# uc1C.net
KiCad netlist of a schematic drawn in Altium Designer
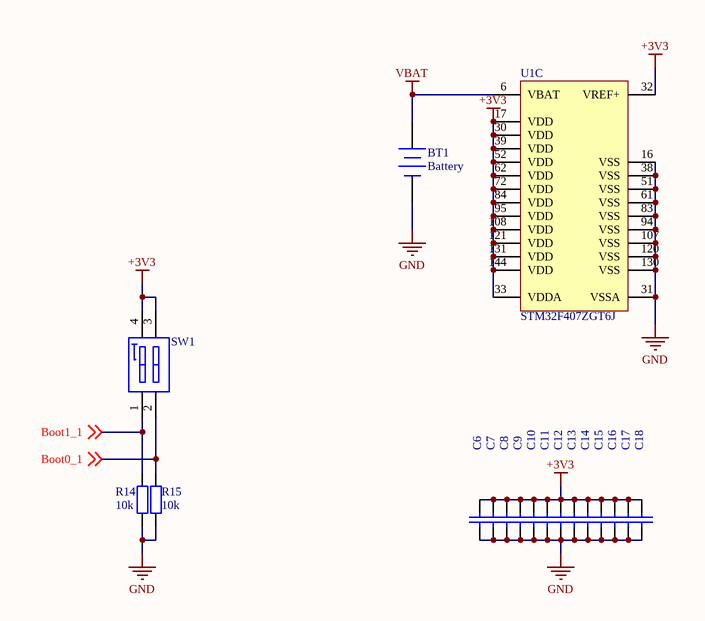
[diagram p0: uc1C.SchDoc]

(export (version "E")
  (design (tool "Eeschema 10.0.6"))
  (components
    (comp (ref "BT1")
      (value "Battery")
      (footprint "2032 SMD Holder")
      (description "Multicell Battery")
      (fields
        (field (name "MANUFACTURER") "MULTICOMP")
        (field (name "MANUFACTURER PART NUMBER") "CH28-2032LF")
        (field (name "PUBLISHER") "Altium Limited")
      )
      (libsource (lib "Miscellaneous Devices") (part "Battery"))
    )
    (comp (ref "C6")
      (value "100nF")
      (footprint "C2012")
      (description "Capacitor")
      (fields
        (field (name "MANUFACTURER") "MULTICOMP")
        (field (name "MANUFACTURER PART NUMBER") "MC0805B104K500CT")
        (field (name "PUBLISHER") "Altium Limited")
      )
      (libsource (lib "Miscellaneous Devices") (part "Cap"))
    )
    (comp (ref "C7")
      (value "100nF")
      (footprint "C2012")
      (description "Capacitor")
      (fields
        (field (name "MANUFACTURER") "MULTICOMP")
        (field (name "MANUFACTURER PART NUMBER") "MC0805B104K500CT")
        (field (name "PUBLISHER") "Altium Limited")
      )
      (libsource (lib "Miscellaneous Devices") (part "Cap"))
    )
    (comp (ref "C8")
      (value "100nF")
      (footprint "C2012")
      (description "Capacitor")
      (fields
        (field (name "MANUFACTURER") "MULTICOMP")
        (field (name "MANUFACTURER PART NUMBER") "MC0805B104K500CT")
        (field (name "PUBLISHER") "Altium Limited")
      )
      (libsource (lib "Miscellaneous Devices") (part "Cap"))
    )
    (comp (ref "C9")
      (value "100nF")
      (footprint "C2012")
      (description "Capacitor")
      (fields
        (field (name "MANUFACTURER") "MULTICOMP")
        (field (name "MANUFACTURER PART NUMBER") "MC0805B104K500CT")
        (field (name "PUBLISHER") "Altium Limited")
      )
      (libsource (lib "Miscellaneous Devices") (part "Cap"))
    )
    (comp (ref "C10")
      (value "100nF")
      (footprint "C2012")
      (description "Capacitor")
      (fields
        (field (name "MANUFACTURER") "MULTICOMP")
        (field (name "MANUFACTURER PART NUMBER") "MC0805B104K500CT")
        (field (name "PUBLISHER") "Altium Limited")
      )
      (libsource (lib "Miscellaneous Devices") (part "Cap"))
    )
    (comp (ref "C11")
      (value "100nF")
      (footprint "C2012")
      (description "Capacitor")
      (fields
        (field (name "MANUFACTURER") "MULTICOMP")
        (field (name "MANUFACTURER PART NUMBER") "MC0805B104K500CT")
        (field (name "PUBLISHER") "Altium Limited")
      )
      (libsource (lib "Miscellaneous Devices") (part "Cap"))
    )
    (comp (ref "C12")
      (value "100nF")
      (footprint "C2012")
      (description "Capacitor")
      (fields
        (field (name "MANUFACTURER") "MULTICOMP")
        (field (name "MANUFACTURER PART NUMBER") "MC0805B104K500CT")
        (field (name "PUBLISHER") "Altium Limited")
      )
      (libsource (lib "Miscellaneous Devices") (part "Cap"))
    )
    (comp (ref "C13")
      (value "100nF")
      (footprint "C2012")
      (description "Capacitor")
      (fields
        (field (name "MANUFACTURER") "MULTICOMP")
        (field (name "MANUFACTURER PART NUMBER") "MC0805B104K500CT")
        (field (name "PUBLISHER") "Altium Limited")
      )
      (libsource (lib "Miscellaneous Devices") (part "Cap"))
    )
    (comp (ref "C14")
      (value "100nF")
      (footprint "C2012")
      (description "Capacitor")
      (fields
        (field (name "MANUFACTURER") "MULTICOMP")
        (field (name "MANUFACTURER PART NUMBER") "MC0805B104K500CT")
        (field (name "PUBLISHER") "Altium Limited")
      )
      (libsource (lib "Miscellaneous Devices") (part "Cap"))
    )
    (comp (ref "C15")
      (value "100nF")
      (footprint "C2012")
      (description "Capacitor")
      (fields
        (field (name "MANUFACTURER") "MULTICOMP")
        (field (name "MANUFACTURER PART NUMBER") "MC0805B104K500CT")
        (field (name "PUBLISHER") "Altium Limited")
      )
      (libsource (lib "Miscellaneous Devices") (part "Cap"))
    )
    (comp (ref "C16")
      (value "100nF")
      (footprint "C2012")
      (description "Capacitor")
      (fields
        (field (name "MANUFACTURER") "MULTICOMP")
        (field (name "MANUFACTURER PART NUMBER") "MC0805B104K500CT")
        (field (name "PUBLISHER") "Altium Limited")
      )
      (libsource (lib "Miscellaneous Devices") (part "Cap"))
    )
    (comp (ref "C17")
      (value "100nF")
      (footprint "C2012")
      (description "Capacitor")
      (fields
        (field (name "MANUFACTURER") "MULTICOMP")
        (field (name "MANUFACTURER PART NUMBER") "MC0805B104K500CT")
        (field (name "PUBLISHER") "Altium Limited")
      )
      (libsource (lib "Miscellaneous Devices") (part "Cap"))
    )
    (comp (ref "C18")
      (value "100nF")
      (footprint "C2012")
      (description "Capacitor")
      (fields
        (field (name "MANUFACTURER") "MULTICOMP")
        (field (name "MANUFACTURER PART NUMBER") "MC0805B104K500CT")
        (field (name "PUBLISHER") "Altium Limited")
      )
      (libsource (lib "Miscellaneous Devices") (part "Cap"))
    )
    (comp (ref "R14")
      (value "10k")
      (footprint "R2012")
      (description "Resistor")
      (fields
        (field (name "MANUFACTURER") "MULTICOMP")
        (field (name "MANUFACTURER PART NUMBER") "MC01W0805110K")
        (field (name "PUBLISHER") "Altium Limited")
      )
      (libsource (lib "") (part "Res2_1"))
    )
    (comp (ref "R15")
      (value "10k")
      (footprint "R2012")
      (description "Resistor")
      (fields
        (field (name "MANUFACTURER") "MULTICOMP")
        (field (name "MANUFACTURER PART NUMBER") "MC01W0805110K")
        (field (name "PUBLISHER") "Altium Limited")
      )
      (libsource (lib "Miscellaneous Devices") (part "Res2"))
    )
    (comp (ref "SW1")
      (value "418121270802")
      (footprint "418121270802")
      (description "WS-DISV 2.54 mm small compact SMD Dip Switch with raised actuator")
      (fields
        (field (name "MANUFACTURER") "Wuerth Elektronik")
        (field (name "MANUFACTURER PART NUMBER") "A6S2104H")
      )
      (libsource (lib "Altium Content Vault") (part "CMP-1438-00002-1"))
    )
    (comp (ref "U1")
      (value "STM32F407ZGT6J")
      (footprint "STM-LQFP144_M")
      (fields (field (name "MANUFACTURER") "STMicroelectronics"))
      (libsource (lib "Altium Content Vault") (part "CMP-0243-00063-2"))
    )
  )
  (nets
    (net (code "1") (name "+3V3") (class "Default")
      (node (ref "C10") (pin "2") (pinfunction "2_2") (pintype "passive"))
      (node (ref "C11") (pin "2") (pinfunction "2_2") (pintype "passive"))
      (node (ref "C12") (pin "2") (pinfunction "2_2") (pintype "passive"))
      (node (ref "C13") (pin "2") (pinfunction "2_2") (pintype "passive"))
      (node (ref "C14") (pin "2") (pinfunction "2_2") (pintype "passive"))
      (node (ref "C15") (pin "2") (pinfunction "2_2") (pintype "passive"))
      (node (ref "C16") (pin "2") (pinfunction "2_2") (pintype "passive"))
      (node (ref "C17") (pin "2") (pinfunction "2_2") (pintype "passive"))
      (node (ref "C18") (pin "2") (pinfunction "2_2") (pintype "passive"))
      (node (ref "C6") (pin "2") (pinfunction "2_2") (pintype "passive"))
      (node (ref "C7") (pin "2") (pinfunction "2_2") (pintype "passive"))
      (node (ref "C8") (pin "2") (pinfunction "2_2") (pintype "passive"))
      (node (ref "C9") (pin "2") (pinfunction "2_2") (pintype "passive"))
      (node (ref "SW1") (pin "3") (pinfunction "3_3") (pintype "passive"))
      (node (ref "SW1") (pin "4") (pinfunction "4_4") (pintype "passive"))
      (node (ref "U1") (pin "108") (pinfunction "VDD_108") (pintype "power_in"))
      (node (ref "U1") (pin "121") (pinfunction "VDD_121") (pintype "power_in"))
      (node (ref "U1") (pin "131") (pinfunction "VDD_131") (pintype "power_in"))
      (node (ref "U1") (pin "144") (pinfunction "VDD_144") (pintype "power_in"))
      (node (ref "U1") (pin "17") (pinfunction "VDD_17") (pintype "power_in"))
      (node (ref "U1") (pin "30") (pinfunction "VDD_30") (pintype "power_in"))
      (node (ref "U1") (pin "32") (pinfunction "VREF+_32") (pintype "power_in"))
      (node (ref "U1") (pin "33") (pinfunction "VDDA_33") (pintype "power_in"))
      (node (ref "U1") (pin "39") (pinfunction "VDD_39") (pintype "power_in"))
      (node (ref "U1") (pin "52") (pinfunction "VDD_52") (pintype "power_in"))
      (node (ref "U1") (pin "62") (pinfunction "VDD_62") (pintype "power_in"))
      (node (ref "U1") (pin "72") (pinfunction "VDD_72") (pintype "power_in"))
      (node (ref "U1") (pin "84") (pinfunction "VDD_84") (pintype "power_in"))
      (node (ref "U1") (pin "95") (pinfunction "VDD_95") (pintype "power_in"))
    )
    (net (code "2") (name "Boot0_1") (class "Default")
      (node (ref "R15") (pin "2") (pinfunction "2_2") (pintype "passive"))
      (node (ref "SW1") (pin "2") (pinfunction "2_2") (pintype "passive"))
    )
    (net (code "3") (name "Boot1_1") (class "Default")
      (node (ref "R14") (pin "1") (pinfunction "1_1") (pintype "passive"))
      (node (ref "SW1") (pin "1") (pinfunction "1_1") (pintype "passive"))
    )
    (net (code "4") (name "GND") (class "Default")
      (node (ref "BT1") (pin "2") (pinfunction "-_2") (pintype "passive"))
      (node (ref "C10") (pin "1") (pinfunction "1_1") (pintype "passive"))
      (node (ref "C11") (pin "1") (pinfunction "1_1") (pintype "passive"))
      (node (ref "C12") (pin "1") (pinfunction "1_1") (pintype "passive"))
      (node (ref "C13") (pin "1") (pinfunction "1_1") (pintype "passive"))
      (node (ref "C14") (pin "1") (pinfunction "1_1") (pintype "passive"))
      (node (ref "C15") (pin "1") (pinfunction "1_1") (pintype "passive"))
      (node (ref "C16") (pin "1") (pinfunction "1_1") (pintype "passive"))
      (node (ref "C17") (pin "1") (pinfunction "1_1") (pintype "passive"))
      (node (ref "C18") (pin "1") (pinfunction "1_1") (pintype "passive"))
      (node (ref "C6") (pin "1") (pinfunction "1_1") (pintype "passive"))
      (node (ref "C7") (pin "1") (pinfunction "1_1") (pintype "passive"))
      (node (ref "C8") (pin "1") (pinfunction "1_1") (pintype "passive"))
      (node (ref "C9") (pin "1") (pinfunction "1_1") (pintype "passive"))
      (node (ref "R14") (pin "2") (pinfunction "2_2") (pintype "passive"))
      (node (ref "R15") (pin "1") (pinfunction "1_1") (pintype "passive"))
      (node (ref "U1") (pin "107") (pinfunction "VSS_107") (pintype "power_in"))
      (node (ref "U1") (pin "120") (pinfunction "VSS_120") (pintype "power_in"))
      (node (ref "U1") (pin "130") (pinfunction "VSS_130") (pintype "power_in"))
      (node (ref "U1") (pin "16") (pinfunction "VSS_16") (pintype "power_in"))
      (node (ref "U1") (pin "31") (pinfunction "VSSA_31") (pintype "power_in"))
      (node (ref "U1") (pin "38") (pinfunction "VSS_38") (pintype "power_in"))
      (node (ref "U1") (pin "51") (pinfunction "VSS_51") (pintype "power_in"))
      (node (ref "U1") (pin "61") (pinfunction "VSS_61") (pintype "power_in"))
      (node (ref "U1") (pin "83") (pinfunction "VSS_83") (pintype "power_in"))
      (node (ref "U1") (pin "94") (pinfunction "VSS_94") (pintype "power_in"))
    )
    (net (code "5") (name "VBAT") (class "Default")
      (node (ref "BT1") (pin "1") (pinfunction "+_1") (pintype "passive"))
      (node (ref "U1") (pin "6") (pinfunction "VBAT_6") (pintype "power_in"))
    )
  )
)
